# Control_Board_2.net
KiCad netlist of a schematic drawn in Altium Designer
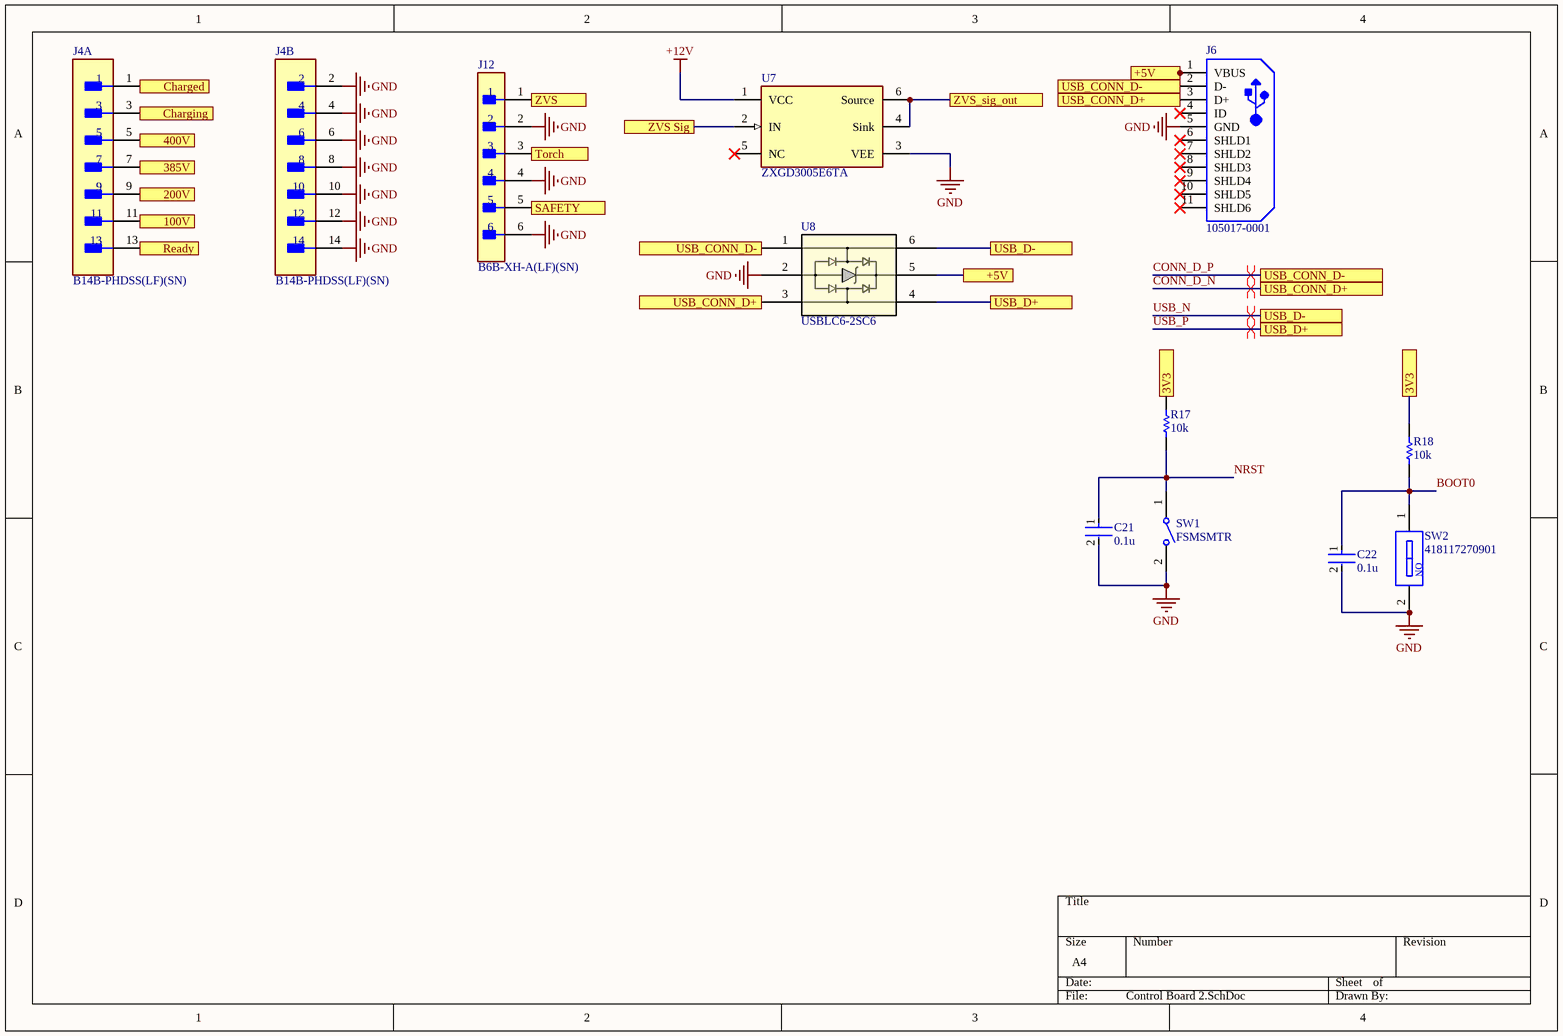
[diagram p0: Control Board 2.SchDoc]

(export (version "E")
  (design (tool "Eeschema 10.0.6"))
  (components
    (comp (ref "C21")
      (value "0.1u")
      (footprint "FP-GRM188-0_1-e0_2_0_55-IPC_A")
      (description "Chip Multilayer Ceramic Capacitors for General Purpose, 0603, 10uF, X5R, 15%, 20%, 6.3V")
      (fields (field (name "VOLTAGE") "6.3V") (field (name "TOLERANCE") "20%"))
      (libsource (lib "Altium Content Vault") (part "02cd4be3c70576c341d710602a673aa"))
    )
    (comp (ref "C22")
      (value "0.1u")
      (footprint "FP-GRM188-0_1-e0_2_0_55-IPC_A")
      (description "Chip Multilayer Ceramic Capacitors for General Purpose, 0603, 10uF, X5R, 15%, 20%, 6.3V")
      (fields (field (name "VOLTAGE") "6.3V") (field (name "TOLERANCE") "20%"))
      (libsource (lib "Altium Content Vault") (part "02cd4be3c70576c341d710602a673aa"))
    )
    (comp (ref "J4")
      (value "B14B-PHDSS(LF)(SN)")
      (footprint "FP-B14B-PHDSS_LF_SN-MFG")
      (description "CONN HEADER VERT 14POS 2MM")
      (libsource (lib "Altium Content Vault") (part "7644e1a88aa4da17242a9b8d8257442"))
    )
    (comp (ref "J6")
      (value "105017-0001")
      (footprint "USB-MICRO-B_V")
      (fields (field (name "MANUFACTURER") "Molex"))
      (libsource (lib "Altium Content Vault") (part "USB-5-6SHLD"))
    )
    (comp (ref "J12")
      (value "B6B-XH-A(LF)(SN)")
      (footprint "FP-B6B-XH-A_LF_SN-MFG")
      (description "CONN HEADER VERT 6POS 2.5MM")
      (libsource (lib "Altium Content Vault") (part "f2cb566baf1c37ab5a3b8e90bbeafd6"))
    )
    (comp (ref "R17")
      (value "10k")
      (footprint "RESC1609X50X30NL8T20")
      (description "Chip Resistor, 10 KOhm, +/- 1%, 100 mW, -55 to 155 degC, 0603 (1608 Metric), RoHS, Tape and Reel")
      (fields (field (name "MANUFACTURER") "Vishay Semiconductor"))
      (libsource (lib "Altium Content Vault") (part "RES-2"))
    )
    (comp (ref "R18")
      (value "10k")
      (footprint "RESC1609X50X30NL8T20")
      (description "Chip Resistor, 10 KOhm, +/- 1%, 100 mW, -55 to 155 degC, 0603 (1608 Metric), RoHS, Tape and Reel")
      (fields (field (name "MANUFACTURER") "Vishay Semiconductor"))
      (libsource (lib "Altium Content Vault") (part "RES-2"))
    )
    (comp (ref "SW1")
      (value "FSMSMTR")
      (footprint "TECO-FSMSMTR_V")
      (description "FSMSM Push Button Switch, 50 mA, -35 to 85 degC, 2-Pin SMD, RoHS, Tape and Reel")
      (fields (field (name "MANUFACTURER") "TE Connectivity"))
      (libsource (lib "Altium Content Vault") (part "SW-SPST-2_C"))
    )
    (comp (ref "SW2")
      (value "418117270901")
      (footprint "418117270901")
      (libsource (lib "Altium Content Vault") (part "DIP-1"))
    )
    (comp (ref "U7")
      (value "ZXGD3005E6TA")
      (footprint "FP-SOT26_SC74R-MFG")
      (description "IC GATE DRVR LOW-SIDE SOT26")
      (fields
        (field (name "OCTOPART") "https://octopart.com/zxgd3005e6ta-diodes+inc.-19727179")
        (field (name "MANUFACTURER") "DIODES INC.")
      )
      (libsource (lib "Altium Content Vault") (part "3d5cd670f3a2fc0eb2369c193e1e526"))
    )
    (comp (ref "U8")
      (value "USBLC6-2SC6")
      (footprint "SOT23-6L_STM")
      (description "No Description Available")
      (fields (field (name "COPYRIGHT") "Copyright (C) 2023 Ultra Librarian. All rights reserved."))
      (libsource (lib "USBLC6-2SC6") (part "USBLC6-2SC6"))
    )
  )
  (nets
    (net (code "1") (name "+12V") (class "Default")
      (node (ref "U7") (pin "1") (pinfunction "VCC_1") (pintype "power_in"))
    )
    (net (code "2") (name "/+5V") (class "Default")
      (node (ref "J6") (pin "1") (pinfunction "VBUS_1") (pintype "passive"))
      (node (ref "U8") (pin "5") (pinfunction "5_5") (pintype "passive"))
    )
    (net (code "3") (name "/3V3") (class "Default")
      (node (ref "R17") (pin "1") (pinfunction "1_1") (pintype "passive"))
      (node (ref "R18") (pin "1") (pinfunction "1_1") (pintype "passive"))
    )
    (net (code "4") (name "/100V") (class "Default")
      (node (ref "J4") (pin "11") (pinfunction "11_11") (pintype "passive"))
    )
    (net (code "5") (name "/200V") (class "Default")
      (node (ref "J4") (pin "9") (pinfunction "9_9") (pintype "passive"))
    )
    (net (code "6") (name "/385V") (class "Default")
      (node (ref "J4") (pin "7") (pinfunction "7_7") (pintype "passive"))
    )
    (net (code "7") (name "/400V") (class "Default")
      (node (ref "J4") (pin "5") (pinfunction "5_5") (pintype "passive"))
    )
    (net (code "8") (name "/BOOT0") (class "Default")
      (node (ref "C22") (pin "1") (pinfunction "1_1") (pintype "passive"))
      (node (ref "R18") (pin "2") (pinfunction "2_2") (pintype "passive"))
      (node (ref "SW2") (pin "1") (pinfunction "1_1") (pintype "passive"))
    )
    (net (code "9") (name "/CONN_D_N") (class "Default")
      (node (ref "J6") (pin "3") (pinfunction "D+_3") (pintype "passive"))
      (node (ref "U8") (pin "3") (pinfunction "3_3") (pintype "passive"))
    )
    (net (code "10") (name "/CONN_D_P") (class "Default")
      (node (ref "J6") (pin "2") (pinfunction "D-_2") (pintype "passive"))
      (node (ref "U8") (pin "1") (pinfunction "1_1") (pintype "passive"))
    )
    (net (code "11") (name "/Charged") (class "Default")
      (node (ref "J4") (pin "1") (pinfunction "1_1") (pintype "passive"))
    )
    (net (code "12") (name "/Charging") (class "Default")
      (node (ref "J4") (pin "3") (pinfunction "3_3") (pintype "passive"))
    )
    (net (code "13") (name "/NRST") (class "Default")
      (node (ref "C21") (pin "1") (pinfunction "1_1") (pintype "passive"))
      (node (ref "R17") (pin "2") (pinfunction "2_2") (pintype "passive"))
      (node (ref "SW1") (pin "1") (pinfunction "1_1") (pintype "passive"))
    )
    (net (code "14") (name "/Ready") (class "Default")
      (node (ref "J4") (pin "13") (pinfunction "13_13") (pintype "passive"))
    )
    (net (code "15") (name "/SAFETY") (class "Default")
      (node (ref "J12") (pin "5") (pinfunction "5_5") (pintype "passive"))
    )
    (net (code "16") (name "/Torch") (class "Default")
      (node (ref "J12") (pin "3") (pinfunction "3_3") (pintype "passive"))
    )
    (net (code "17") (name "/USB_N") (class "Default")
      (node (ref "U8") (pin "6") (pinfunction "6_6") (pintype "passive"))
    )
    (net (code "18") (name "/USB_P") (class "Default")
      (node (ref "U8") (pin "4") (pinfunction "4_4") (pintype "passive"))
    )
    (net (code "19") (name "/ZVS") (class "Default")
      (node (ref "J12") (pin "1") (pinfunction "1_1") (pintype "passive"))
    )
    (net (code "20") (name "/ZVS Sig") (class "Default")
      (node (ref "U7") (pin "2") (pinfunction "IN_2") (pintype "input"))
    )
    (net (code "21") (name "/ZVS_sig_out") (class "Default")
      (node (ref "U7") (pin "4") (pinfunction "Sink_4") (pintype "passive"))
      (node (ref "U7") (pin "6") (pinfunction "Source_6") (pintype "passive"))
    )
    (net (code "22") (name "GND") (class "Default")
      (node (ref "C21") (pin "2") (pinfunction "2_2") (pintype "passive"))
      (node (ref "C22") (pin "2") (pinfunction "2_2") (pintype "passive"))
      (node (ref "J12") (pin "2") (pinfunction "2_2") (pintype "passive"))
      (node (ref "J12") (pin "4") (pinfunction "4_4") (pintype "passive"))
      (node (ref "J12") (pin "6") (pinfunction "6_6") (pintype "passive"))
      (node (ref "J4") (pin "10") (pinfunction "10_10") (pintype "passive"))
      (node (ref "J4") (pin "12") (pinfunction "12_12") (pintype "passive"))
      (node (ref "J4") (pin "14") (pinfunction "14_14") (pintype "passive"))
      (node (ref "J4") (pin "2") (pinfunction "2_2") (pintype "passive"))
      (node (ref "J4") (pin "4") (pinfunction "4_4") (pintype "passive"))
      (node (ref "J4") (pin "6") (pinfunction "6_6") (pintype "passive"))
      (node (ref "J4") (pin "8") (pinfunction "8_8") (pintype "passive"))
      (node (ref "J6") (pin "5") (pinfunction "GND_5") (pintype "passive"))
      (node (ref "SW1") (pin "2") (pinfunction "2_2") (pintype "passive"))
      (node (ref "SW2") (pin "2") (pinfunction "2_2") (pintype "passive"))
      (node (ref "U7") (pin "3") (pinfunction "VEE_3") (pintype "power_in"))
      (node (ref "U8") (pin "2") (pinfunction "2_2") (pintype "passive"))
    )
    (net (code "23") (name "unconnected-(J6-ID-Pad4)") (class "Default")
      (node (ref "J6") (pin "4") (pinfunction "ID_4") (pintype "passive+no_connect"))
    )
    (net (code "24") (name "unconnected-(J6-SHLD1-Pad6)") (class "Default")
      (node (ref "J6") (pin "6") (pinfunction "SHLD1_6") (pintype "passive+no_connect"))
    )
    (net (code "25") (name "unconnected-(J6-SHLD2-Pad7)") (class "Default")
      (node (ref "J6") (pin "7") (pinfunction "SHLD2_7") (pintype "passive+no_connect"))
    )
    (net (code "26") (name "unconnected-(J6-SHLD3-Pad8)") (class "Default")
      (node (ref "J6") (pin "8") (pinfunction "SHLD3_8") (pintype "passive+no_connect"))
    )
    (net (code "27") (name "unconnected-(J6-SHLD4-Pad9)") (class "Default")
      (node (ref "J6") (pin "9") (pinfunction "SHLD4_9") (pintype "passive+no_connect"))
    )
    (net (code "28") (name "unconnected-(J6-SHLD5-Pad10)") (class "Default")
      (node (ref "J6") (pin "10") (pinfunction "SHLD5_10") (pintype "passive+no_connect"))
    )
    (net (code "29") (name "unconnected-(J6-SHLD6-Pad11)") (class "Default")
      (node (ref "J6") (pin "11") (pinfunction "SHLD6_11") (pintype "passive+no_connect"))
    )
    (net (code "30") (name "unconnected-(U7-NC-Pad5)") (class "Default")
      (node (ref "U7") (pin "5") (pinfunction "NC_5") (pintype "passive+no_connect"))
    )
  )
)
